# 05-AT86RF215IQ-FEM.net
KiCad netlist of a schematic drawn in Altium Designer
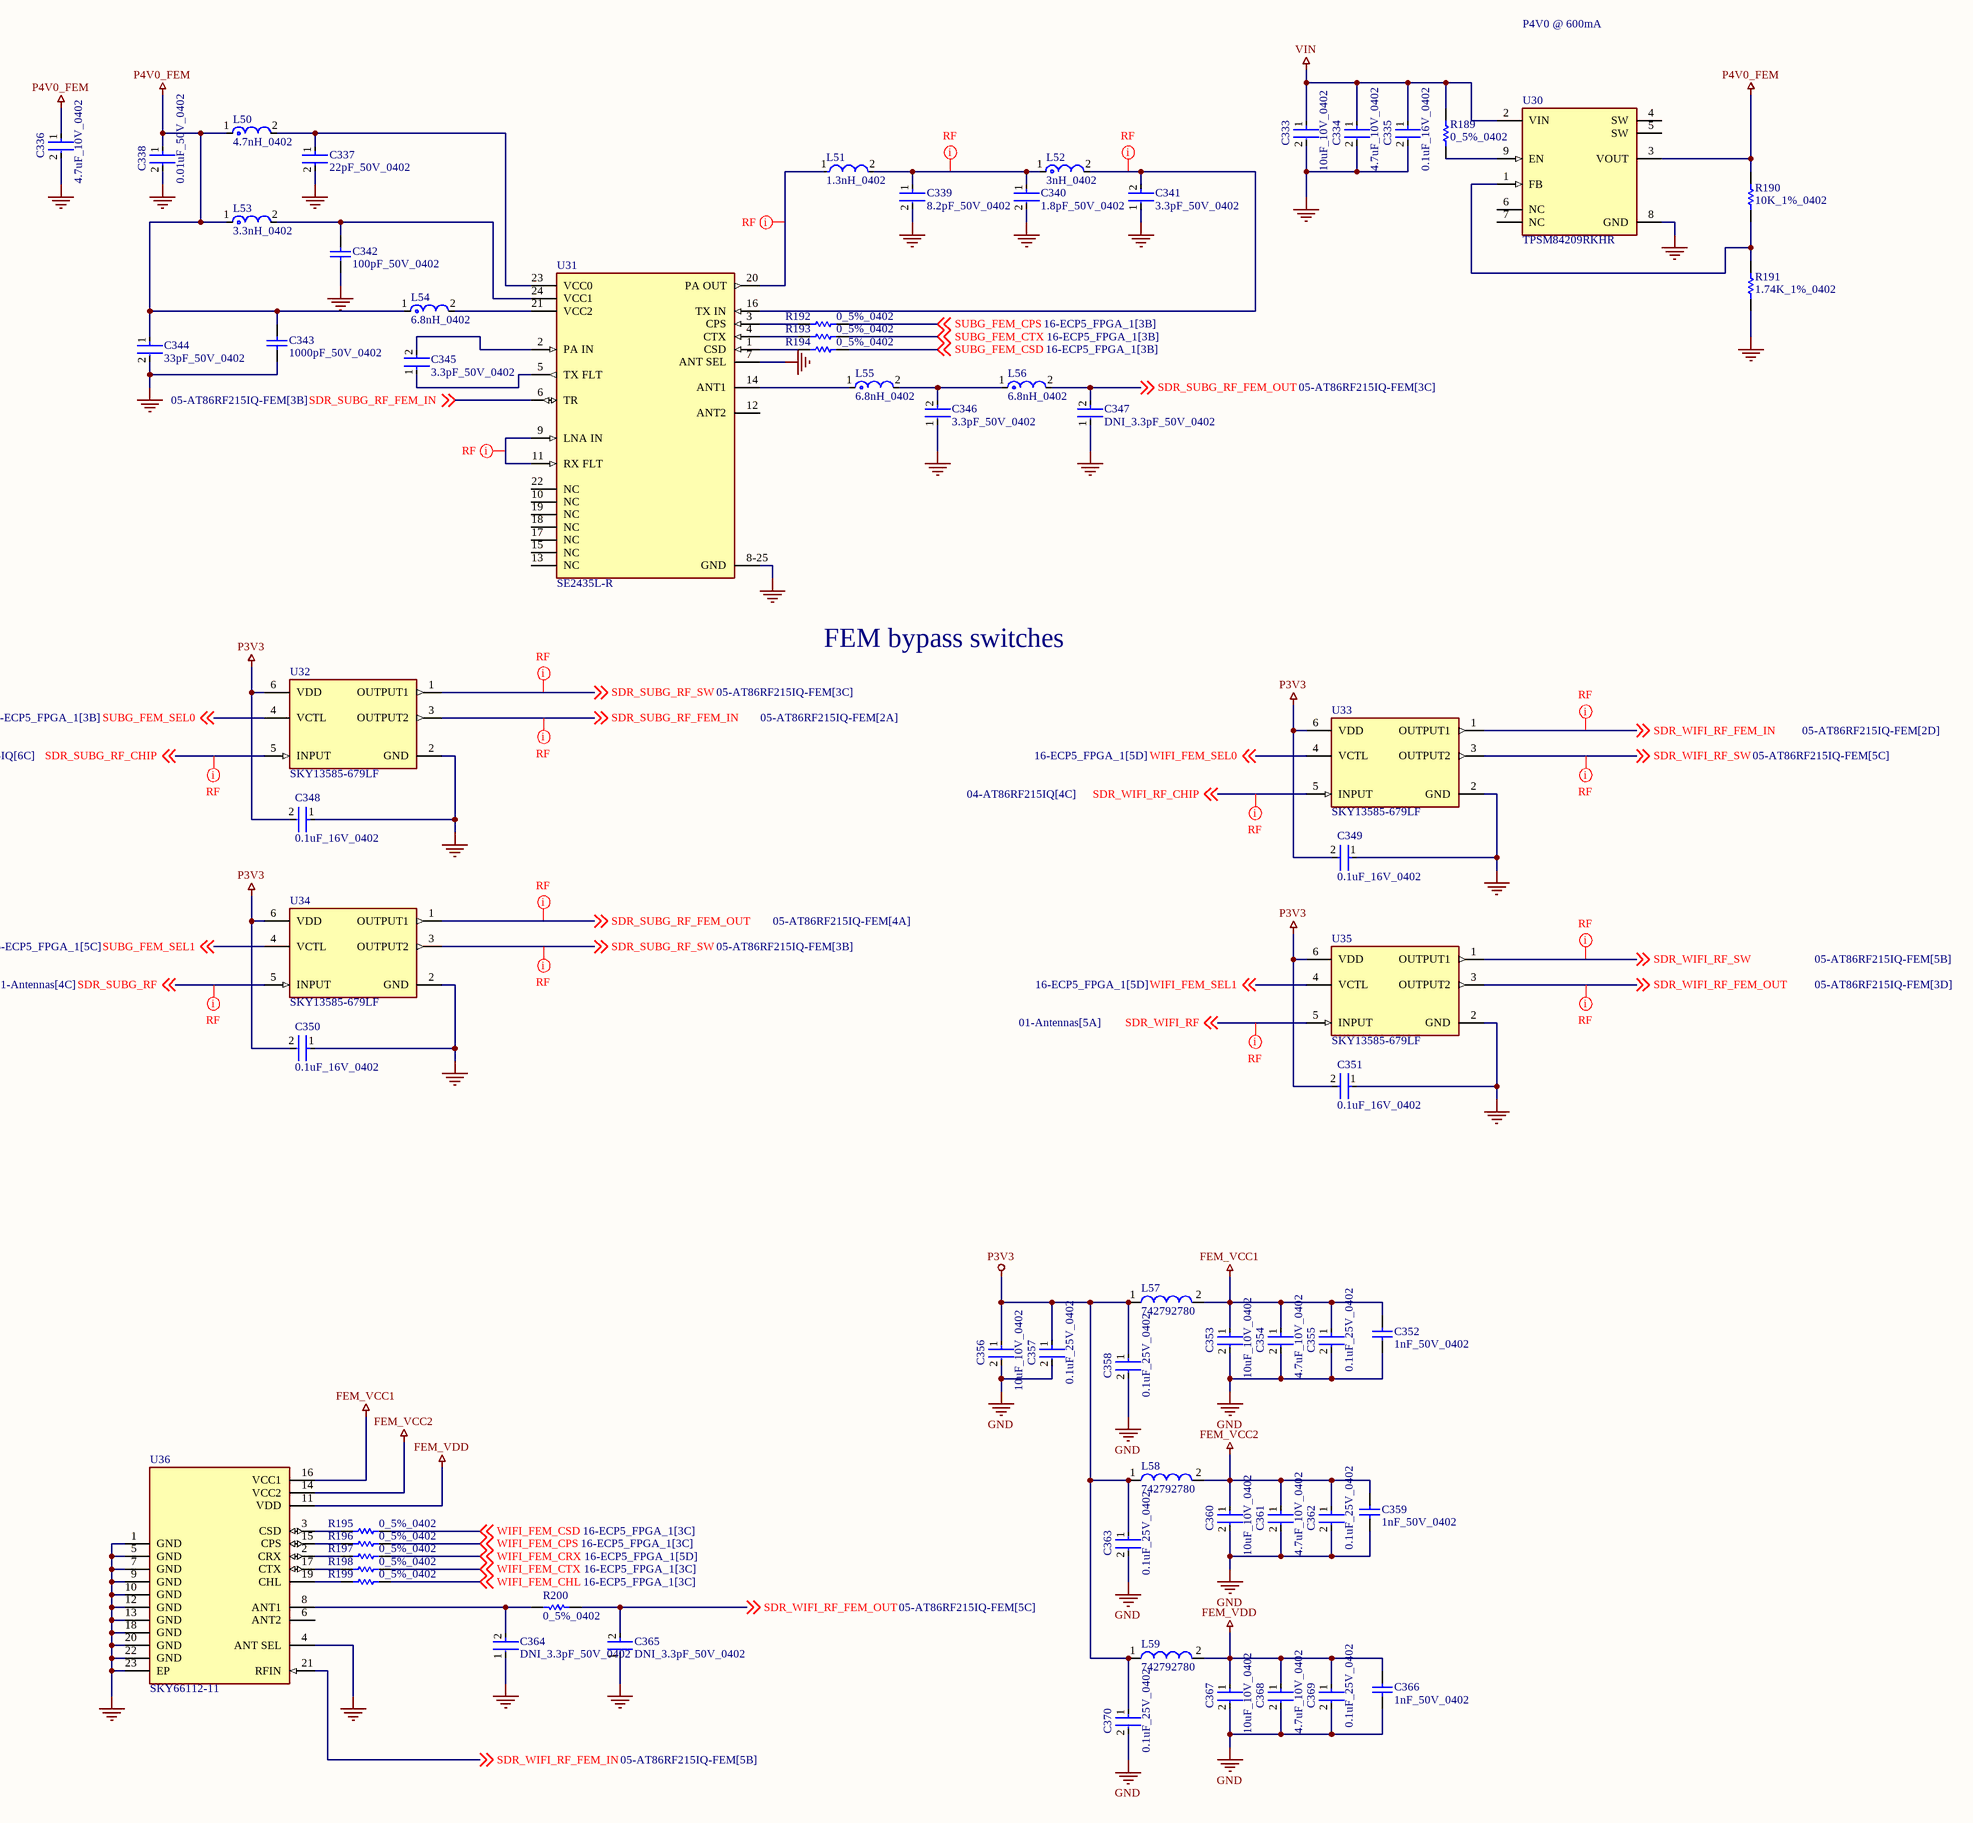
[diagram p0: 05-AT86RF215IQ-FEM.SchDoc]

(export (version "E")
  (design (tool "Eeschema 10.0.6"))
  (components
    (comp (ref "C333")
      (value "10uF_10V_0402")
      (footprint "FP-CL05A106MP5NUNC-MFG")
      (description "CAP CER 10UF 10V X5R 0402")
      (fields
        (field (name "OCTOPART") "https://octopart.com/cl05a106mp5nunc-samsung-22457395")
        (field (name "TOLERANCE") "20%")
      )
      (libsource (lib "Altium Content Vault") (part "b4654b650e69147ec39a6b967a45e02"))
    )
    (comp (ref "C334")
      (value "4.7uF_10V_0402")
      (footprint "FP-C1005-050-0_15-MFG")
      (description "CAP CER 4.7UF 10V X5R 0402")
      (fields (field (name "TOLERANCE") "10%"))
      (libsource (lib "Altium Content Vault") (part "b4654b650e69147ec39a6b967a45e02"))
    )
    (comp (ref "C335")
      (value "0.1uF_16V_0402")
      (footprint "FP-C0402-BB-MFG")
      (description "CAP CER 0.1UF 16V 5% X7R 0402")
      (fields
        (field (name "MANUFACTURER") "Kemet")
        (field (name "MANUFACTURER PART NUMBER") "C0402C104J4RACTU")
      )
      (libsource (lib "Altium Content Vault") (part "b4654b650e69147ec39a6b967a45e02"))
    )
    (comp (ref "C336")
      (value "4.7uF_10V_0402")
      (footprint "FP-C1005-050-0_15-MFG")
      (description "CAP CER 4.7UF 10V X5R 0402")
      (fields (field (name "TOLERANCE") "10%"))
      (libsource (lib "Altium Content Vault") (part "b4654b650e69147ec39a6b967a45e02"))
    )
    (comp (ref "C337")
      (value "22pF_50V_0402")
      (footprint "FP-0402-L_1_0_1-W_0_5_0_1-MFG")
      (description "General Purpose Ceramic Capacitor, 0402, 22pF, 5%, C0G, 30ppm/°C, 50V")
      (fields (field (name "VOLTAGE") "50V") (field (name "TOLERANCE") "5%"))
      (libsource (lib "Altium Content Vault") (part "b4654b650e69147ec39a6b967a45e02"))
    )
    (comp (ref "C338")
      (value "0.01uF_50V_0402")
      (footprint "FP-GCM155-0_05-IPC_C")
      (description "Ceramic Capacitor for Automotive 10nF ±10% 50VDC X7R 0402 Paper T/R")
      (fields (field (name "TOLERANCE") "10%") (field (name "VOLTAGE") "50V"))
      (libsource (lib "Altium Content Vault") (part "02cd4be3c70576c341d710602a673aa"))
    )
    (comp (ref "C339")
      (value "8.2pF_50V_0402")
      (footprint "FP-GJM155-0_05-IPC_C")
      (description "Multi-Layer Ceramic Capacitor 8.2pF C0G  ±0.25pF 0402 Paper T/R")
      (fields (field (name "VOLTAGE") "50V"))
      (libsource (lib "Altium Content Vault") (part "02cd4be3c70576c341d710602a673aa"))
    )
    (comp (ref "C340")
      (value "1.8pF_50V_0402")
      (footprint "FP-GJM155-0_05-IPC_B")
      (description "Multi-Layer Ceramic Capacitor 1.8pF C0G  ±0.1pF 0402 Paper T/R")
      (fields (field (name "VOLTAGE") "50V"))
      (libsource (lib "Altium Content Vault") (part "02cd4be3c70576c341d710602a673aa"))
    )
    (comp (ref "C341")
      (value "3.3pF_50V_0402")
      (footprint "FP-CBR04C-MFG")
      (description "CAP CER 3.3PF 50V C0G/NP0 0402")
      (fields (field (name "MANUFACTURER PART NUMBER") "CBR04C339C5GAC") (field (name "TOLERANCE") "0.25 pF"))
      (libsource (lib "Altium Content Vault") (part "236180d848d6139a670b325ea6854c9"))
    )
    (comp (ref "C342")
      (value "100pF_50V_0402")
      (footprint "CAPC1005X55X25ML05T10")
      (fields (field (name "MANUFACTURER") "Murata") (field (name "PART NUMBER") "GRM1555C1H101JA01D"))
      (libsource (lib "Altium Content Vault") (part "CAP"))
    )
    (comp (ref "C343")
      (value "1000pF_50V_0402")
      (footprint "CAPC1005X55X25ML5T10")
      (description "Chip Capacitor, 1 nF, +/- 10%, 50 V, -55 to 125 degC, 0402 (1005 Metric), RoHS, Tape and Reel")
      (fields (field (name "TOLERANCE") "10%"))
      (libsource (lib "Altium Content Vault") (part "CAP-NP-2"))
    )
    (comp (ref "C344")
      (value "33pF_50V_0402")
      (footprint "FP-0402-L_1_0_1-W_0_5_0_1-IPC_A")
      (description "General Purpose Ceramic Capacitor, 0402, 33pF, 5%, C0G, 30ppm/°C, 50V")
      (fields (field (name "TOLERANCE") "5%") (field (name "VOLTAGE") "50V"))
      (libsource (lib "Altium Content Vault") (part "b4654b650e69147ec39a6b967a45e02"))
    )
    (comp (ref "C345")
      (value "3.3pF_50V_0402")
      (footprint "FP-GCM155-0_05-IPC_B")
      (description "Ceramic Capacitor for Automotive 3.3pF ±0.25pF 50VDC C0G 0402 Paper T/R")
      (libsource (lib "Altium Content Vault") (part "02cd4be3c70576c341d710602a673aa"))
    )
    (comp (ref "C346")
      (value "3.3pF_50V_0402")
      (footprint "FP-CBR04C-MFG")
      (description "CAP CER 3.3PF 50V C0G/NP0 0402")
      (fields (field (name "MANUFACTURER PART NUMBER") "CBR04C339C5GAC") (field (name "TOLERANCE") "0.25 pF"))
      (libsource (lib "Altium Content Vault") (part "236180d848d6139a670b325ea6854c9"))
    )
    (comp (ref "C347")
      (value "DNI_3.3pF_50V_0402")
      (footprint "FP-CBR04C-MFG")
      (description "CAP CER 3.3PF 50V C0G/NP0 0402")
      (fields (field (name "MANUFACTURER PART NUMBER") "CBR04C339C5GAC") (field (name "TOLERANCE") "0.25 pF"))
      (libsource (lib "Altium Content Vault") (part "236180d848d6139a670b325ea6854c9"))
    )
    (comp (ref "C348")
      (value "0.1uF_16V_0402")
      (footprint "FP-C0402-BB-MFG")
      (description "CAP CER 0.1UF 16V 5% X7R 0402")
      (fields
        (field (name "MANUFACTURER") "Kemet")
        (field (name "MANUFACTURER PART NUMBER") "C0402C104J4RACTU")
      )
      (libsource (lib "Altium Content Vault") (part "b4654b650e69147ec39a6b967a45e02"))
    )
    (comp (ref "C349")
      (value "0.1uF_16V_0402")
      (footprint "FP-C0402-BB-MFG")
      (description "CAP CER 0.1UF 16V 5% X7R 0402")
      (fields
        (field (name "MANUFACTURER") "Kemet")
        (field (name "MANUFACTURER PART NUMBER") "C0402C104J4RACTU")
      )
      (libsource (lib "Altium Content Vault") (part "b4654b650e69147ec39a6b967a45e02"))
    )
    (comp (ref "C350")
      (value "0.1uF_16V_0402")
      (footprint "FP-C0402-BB-MFG")
      (description "CAP CER 0.1UF 16V 5% X7R 0402")
      (fields
        (field (name "MANUFACTURER") "Kemet")
        (field (name "MANUFACTURER PART NUMBER") "C0402C104J4RACTU")
      )
      (libsource (lib "Altium Content Vault") (part "b4654b650e69147ec39a6b967a45e02"))
    )
    (comp (ref "C351")
      (value "0.1uF_16V_0402")
      (footprint "FP-C0402-BB-MFG")
      (description "CAP CER 0.1UF 16V 5% X7R 0402")
      (fields
        (field (name "MANUFACTURER") "Kemet")
        (field (name "MANUFACTURER PART NUMBER") "C0402C104J4RACTU")
      )
      (libsource (lib "Altium Content Vault") (part "b4654b650e69147ec39a6b967a45e02"))
    )
    (comp (ref "C352")
      (value "1nF_50V_0402")
      (footprint "CAPC1005X55X25ML5T10")
      (description "Chip Capacitor, 1 nF, +/- 10%, 50 V, -55 to 125 degC, 0402 (1005 Metric), RoHS, Tape and Reel")
      (fields (field (name "TOLERANCE") "10%"))
      (libsource (lib "Altium Content Vault") (part "CAP-NP-2"))
    )
    (comp (ref "C353")
      (value "10uF_10V_0402")
      (footprint "FP-CL05A106MP5NUNC-MFG")
      (description "CAP CER 10UF 10V X5R 0402")
      (fields
        (field (name "OCTOPART") "https://octopart.com/cl05a106mp5nunc-samsung-22457395")
        (field (name "TOLERANCE") "20%")
      )
      (libsource (lib "Altium Content Vault") (part "b4654b650e69147ec39a6b967a45e02"))
    )
    (comp (ref "C354")
      (value "4.7uF_10V_0402")
      (footprint "FP-C1005-050-0_15-MFG")
      (description "CAP CER 4.7UF 10V X5R 0402")
      (fields (field (name "TOLERANCE") "10%"))
      (libsource (lib "Altium Content Vault") (part "b4654b650e69147ec39a6b967a45e02"))
    )
    (comp (ref "C355")
      (value "0.1uF_25V_0402")
      (footprint "FP-0402-L_1_0_1-W_0_5_0_1-IPC_C")
      (description "General Purpose Ceramic Capacitor, 0402, 100nF, 10%, X7R, 15%, 25V")
      (fields (field (name "VOLTAGE") "25V") (field (name "TOLERANCE") "10%"))
      (libsource (lib "Altium Content Vault") (part "b4654b650e69147ec39a6b967a45e02"))
    )
    (comp (ref "C356")
      (value "10uF_10V_0402")
      (footprint "FP-CL05A106MP5NUNC-MFG")
      (description "CAP CER 10UF 10V X5R 0402")
      (fields
        (field (name "OCTOPART") "https://octopart.com/cl05a106mp5nunc-samsung-22457395")
        (field (name "TOLERANCE") "20%")
      )
      (libsource (lib "Altium Content Vault") (part "b4654b650e69147ec39a6b967a45e02"))
    )
    (comp (ref "C357")
      (value "0.1uF_25V_0402")
      (footprint "FP-0402-L_1_0_1-W_0_5_0_1-IPC_C")
      (description "General Purpose Ceramic Capacitor, 0402, 100nF, 10%, X7R, 15%, 25V")
      (fields (field (name "VOLTAGE") "25V") (field (name "TOLERANCE") "10%"))
      (libsource (lib "Altium Content Vault") (part "b4654b650e69147ec39a6b967a45e02"))
    )
    (comp (ref "C358")
      (value "0.1uF_25V_0402")
      (footprint "FP-0402-L_1_0_1-W_0_5_0_1-IPC_C")
      (description "General Purpose Ceramic Capacitor, 0402, 100nF, 10%, X7R, 15%, 25V")
      (fields (field (name "VOLTAGE") "25V") (field (name "TOLERANCE") "10%"))
      (libsource (lib "Altium Content Vault") (part "b4654b650e69147ec39a6b967a45e02"))
    )
    (comp (ref "C359")
      (value "1nF_50V_0402")
      (footprint "CAPC1005X55X25ML5T10")
      (description "Chip Capacitor, 1 nF, +/- 10%, 50 V, -55 to 125 degC, 0402 (1005 Metric), RoHS, Tape and Reel")
      (fields (field (name "TOLERANCE") "10%"))
      (libsource (lib "Altium Content Vault") (part "CAP-NP-2"))
    )
    (comp (ref "C360")
      (value "10uF_10V_0402")
      (footprint "FP-CL05A106MP5NUNC-MFG")
      (description "CAP CER 10UF 10V X5R 0402")
      (fields
        (field (name "OCTOPART") "https://octopart.com/cl05a106mp5nunc-samsung-22457395")
        (field (name "TOLERANCE") "20%")
      )
      (libsource (lib "Altium Content Vault") (part "b4654b650e69147ec39a6b967a45e02"))
    )
    (comp (ref "C361")
      (value "4.7uF_10V_0402")
      (footprint "FP-C1005-050-0_15-MFG")
      (description "CAP CER 4.7UF 10V X5R 0402")
      (fields (field (name "TOLERANCE") "10%"))
      (libsource (lib "Altium Content Vault") (part "b4654b650e69147ec39a6b967a45e02"))
    )
    (comp (ref "C362")
      (value "0.1uF_25V_0402")
      (footprint "FP-0402-L_1_0_1-W_0_5_0_1-IPC_C")
      (description "General Purpose Ceramic Capacitor, 0402, 100nF, 10%, X7R, 15%, 25V")
      (fields (field (name "VOLTAGE") "25V") (field (name "TOLERANCE") "10%"))
      (libsource (lib "Altium Content Vault") (part "b4654b650e69147ec39a6b967a45e02"))
    )
    (comp (ref "C363")
      (value "0.1uF_25V_0402")
      (footprint "FP-0402-L_1_0_1-W_0_5_0_1-IPC_C")
      (description "General Purpose Ceramic Capacitor, 0402, 100nF, 10%, X7R, 15%, 25V")
      (fields (field (name "VOLTAGE") "25V") (field (name "TOLERANCE") "10%"))
      (libsource (lib "Altium Content Vault") (part "b4654b650e69147ec39a6b967a45e02"))
    )
    (comp (ref "C364")
      (value "DNI_3.3pF_50V_0402")
      (footprint "FP-CBR04C-MFG")
      (description "CAP CER 3.3PF 50V C0G/NP0 0402")
      (fields (field (name "MANUFACTURER PART NUMBER") "CBR04C339C5GAC") (field (name "TOLERANCE") "0.25 pF"))
      (libsource (lib "Altium Content Vault") (part "236180d848d6139a670b325ea6854c9"))
    )
    (comp (ref "C365")
      (value "DNI_3.3pF_50V_0402")
      (footprint "FP-CBR04C-MFG")
      (description "CAP CER 3.3PF 50V C0G/NP0 0402")
      (fields (field (name "MANUFACTURER PART NUMBER") "CBR04C339C5GAC") (field (name "TOLERANCE") "0.25 pF"))
      (libsource (lib "Altium Content Vault") (part "236180d848d6139a670b325ea6854c9"))
    )
    (comp (ref "C366")
      (value "1nF_50V_0402")
      (footprint "CAPC1005X55X25ML5T10")
      (description "Chip Capacitor, 1 nF, +/- 10%, 50 V, -55 to 125 degC, 0402 (1005 Metric), RoHS, Tape and Reel")
      (fields (field (name "TOLERANCE") "10%"))
      (libsource (lib "Altium Content Vault") (part "CAP-NP-2"))
    )
    (comp (ref "C367")
      (value "10uF_10V_0402")
      (footprint "FP-CL05A106MP5NUNC-MFG")
      (description "CAP CER 10UF 10V X5R 0402")
      (fields
        (field (name "OCTOPART") "https://octopart.com/cl05a106mp5nunc-samsung-22457395")
        (field (name "TOLERANCE") "20%")
      )
      (libsource (lib "Altium Content Vault") (part "b4654b650e69147ec39a6b967a45e02"))
    )
    (comp (ref "C368")
      (value "4.7uF_10V_0402")
      (footprint "FP-C1005-050-0_15-MFG")
      (description "CAP CER 4.7UF 10V X5R 0402")
      (fields (field (name "TOLERANCE") "10%"))
      (libsource (lib "Altium Content Vault") (part "b4654b650e69147ec39a6b967a45e02"))
    )
    (comp (ref "C369")
      (value "0.1uF_25V_0402")
      (footprint "FP-0402-L_1_0_1-W_0_5_0_1-IPC_C")
      (description "General Purpose Ceramic Capacitor, 0402, 100nF, 10%, X7R, 15%, 25V")
      (fields (field (name "VOLTAGE") "25V") (field (name "TOLERANCE") "10%"))
      (libsource (lib "Altium Content Vault") (part "b4654b650e69147ec39a6b967a45e02"))
    )
    (comp (ref "C370")
      (value "0.1uF_25V_0402")
      (footprint "FP-0402-L_1_0_1-W_0_5_0_1-IPC_C")
      (description "General Purpose Ceramic Capacitor, 0402, 100nF, 10%, X7R, 15%, 25V")
      (fields (field (name "VOLTAGE") "25V") (field (name "TOLERANCE") "10%"))
      (libsource (lib "Altium Content Vault") (part "b4654b650e69147ec39a6b967a45e02"))
    )
    (comp (ref "L50")
      (value "4.7nH_0402")
      (footprint "FP-LQG15HH_02-IPC_B")
      (description "Multilayer type RF Inductor 4.7nH ±0.2nH 0.16Ω 700mA 0402")
      (libsource (lib "Altium Content Vault") (part "4cc4b267dca4c8e51f7102f422741d8"))
    )
    (comp (ref "L51")
      (value "1.3nH_0402")
      (footprint "FP-LQW15AN_00-W0_6-0_1-MFG")
      (description "Wire Wound RF Inductor 1.3nH ±0.2nH 1200mA 0.017Ω 0402 (1005)")
      (libsource (lib "Altium Content Vault") (part "725321dda6339637d4d059423bc1c3c"))
    )
    (comp (ref "L52")
      (value "3nH_0402")
      (footprint "FP-LQG15HH_02-IPC_A")
      (description "Multilayer type RF Inductor 3nH ±0.3nH 0.125Ω 800mA 0402")
      (libsource (lib "Altium Content Vault") (part "4cc4b267dca4c8e51f7102f422741d8"))
    )
    (comp (ref "L53")
      (value "3.3nH_0402")
      (footprint "FP-LQG15HH_02-IPC_B")
      (description "Multilayer type RF Inductor 3.3nH ±0.3nH 0.125Ω 800mA 0402")
      (libsource (lib "Altium Content Vault") (part "4cc4b267dca4c8e51f7102f422741d8"))
    )
    (comp (ref "L54")
      (value "6.8nH_0402")
      (footprint "FP-LQG15HH_02-IPC_A")
      (description "Multilayer type RF Inductor 6.8nH ±5% 0.22Ω 600mA 0402")
      (fields (field (name "TOLERANCE") "5%"))
      (libsource (lib "Altium Content Vault") (part "4cc4b267dca4c8e51f7102f422741d8"))
    )
    (comp (ref "L55")
      (value "6.8nH_0402")
      (footprint "FP-LQG15HH_02-IPC_A")
      (description "Multilayer type RF Inductor 6.8nH ±5% 0.22Ω 600mA 0402")
      (fields (field (name "TOLERANCE") "5%"))
      (libsource (lib "Altium Content Vault") (part "4cc4b267dca4c8e51f7102f422741d8"))
    )
    (comp (ref "L56")
      (value "6.8nH_0402")
      (footprint "FP-LQG15HH_02-IPC_A")
      (description "Multilayer type RF Inductor 6.8nH ±5% 0.22Ω 600mA 0402")
      (fields (field (name "TOLERANCE") "5%"))
      (libsource (lib "Altium Content Vault") (part "4cc4b267dca4c8e51f7102f422741d8"))
    )
    (comp (ref "L57")
      (value "742792780")
      (footprint "SMD-0402")
      (description "SMD EMI Suppression Ferrite Bead WE-CBF, Z = 220 Ohm")
      (libsource (lib "Altium Content Vault") (part "PAS-IND-INDUCTOR-2"))
    )
    (comp (ref "L58")
      (value "742792780")
      (footprint "SMD-0402")
      (description "SMD EMI Suppression Ferrite Bead WE-CBF, Z = 220 Ohm")
      (libsource (lib "Altium Content Vault") (part "PAS-IND-INDUCTOR-2"))
    )
    (comp (ref "L59")
      (value "742792780")
      (footprint "SMD-0402")
      (description "SMD EMI Suppression Ferrite Bead WE-CBF, Z = 220 Ohm")
      (libsource (lib "Altium Content Vault") (part "PAS-IND-INDUCTOR-2"))
    )
    (comp (ref "R189")
      (value "0_5%_0402")
      (footprint "RESC1005X40X25NL05T10")
      (fields (field (name "MANUFACTURER") "Panasonic") (field (name "PART NUMBER") "ERJ-U020R00X"))
      (libsource (lib "Altium Content Vault") (part "RES"))
    )
    (comp (ref "R190")
      (value "10K_1%_0402")
      (footprint "RESC1005X40X25LL05T10")
      (fields (field (name "PART NUMBER") "RC0402FR-0710KL") (field (name "MANUFACTURER") "Yageo / Phycomp"))
      (libsource (lib "Altium Content Vault") (part "RES"))
    )
    (comp (ref "R191")
      (value "1.74K_1%_0402")
      (footprint "RESC1005X40X25NL05T05")
      (fields (field (name "MANUFACTURER") "Panasonic") (field (name "PART NUMBER") "ERJ-2RKF1741X"))
      (libsource (lib "Altium Content Vault") (part "RES"))
    )
    (comp (ref "R192")
      (value "0_5%_0402")
      (footprint "RESC1005X40X25NL05T10")
      (fields (field (name "MANUFACTURER") "Panasonic") (field (name "PART NUMBER") "ERJ-U020R00X"))
      (libsource (lib "Altium Content Vault") (part "RES"))
    )
    (comp (ref "R193")
      (value "0_5%_0402")
      (footprint "RESC1005X40X25NL05T10")
      (fields (field (name "MANUFACTURER") "Panasonic") (field (name "PART NUMBER") "ERJ-U020R00X"))
      (libsource (lib "Altium Content Vault") (part "RES"))
    )
    (comp (ref "R194")
      (value "0_5%_0402")
      (footprint "RESC1005X40X25NL05T10")
      (fields (field (name "MANUFACTURER") "Panasonic") (field (name "PART NUMBER") "ERJ-U020R00X"))
      (libsource (lib "Altium Content Vault") (part "RES"))
    )
    (comp (ref "R195")
      (value "0_5%_0402")
      (footprint "RESC1005X40X25NL05T10")
      (fields (field (name "MANUFACTURER") "Panasonic") (field (name "PART NUMBER") "ERJ-U020R00X"))
      (libsource (lib "Altium Content Vault") (part "RES"))
    )
    (comp (ref "R196")
      (value "0_5%_0402")
      (footprint "RESC1005X40X25NL05T10")
      (fields (field (name "MANUFACTURER") "Panasonic") (field (name "PART NUMBER") "ERJ-U020R00X"))
      (libsource (lib "Altium Content Vault") (part "RES"))
    )
    (comp (ref "R197")
      (value "0_5%_0402")
      (footprint "RESC1005X40X25NL05T10")
      (fields (field (name "MANUFACTURER") "Panasonic") (field (name "PART NUMBER") "ERJ-U020R00X"))
      (libsource (lib "Altium Content Vault") (part "RES"))
    )
    (comp (ref "R198")
      (value "0_5%_0402")
      (footprint "RESC1005X40X25NL05T10")
      (fields (field (name "MANUFACTURER") "Panasonic") (field (name "PART NUMBER") "ERJ-U020R00X"))
      (libsource (lib "Altium Content Vault") (part "RES"))
    )
    (comp (ref "R199")
      (value "0_5%_0402")
      (footprint "RESC1005X40X25NL05T10")
      (fields (field (name "MANUFACTURER") "Panasonic") (field (name "PART NUMBER") "ERJ-U020R00X"))
      (libsource (lib "Altium Content Vault") (part "RES"))
    )
    (comp (ref "R200")
      (value "0_5%_0402")
      (footprint "RESC1005X40X25NL05T10")
      (fields (field (name "MANUFACTURER") "Panasonic") (field (name "PART NUMBER") "ERJ-U020R00X"))
      (libsource (lib "Altium Content Vault") (part "RES"))
    )
    (comp (ref "U30")
      (value "TPSM84209RKHR")
      (footprint "FP-RKH0009A-MFG")
      (description "DC DC CONVERTER 1.2-6V")
      (libsource (lib "Altium Content Vault") (part "5195406eaf4ebe97fbc3c0702d316f5"))
    )
    (comp (ref "U31")
      (value "SE2435L-R")
      (footprint "FP-SE2435L-R-MFG")
      (description "IC FRONT END 930MHZ ISM 24QFN")
      (libsource (lib "Altium Content Vault") (part "3362008c0bbccc1bfff27db7c35ca37"))
    )
    (comp (ref "U32")
      (value "SKY13585-679LF")
      (footprint "FP-SKY13585-679LF-MFG")
      (description "IC RF SWITCH SPDT 6GHZ 6MLPD")
      (libsource (lib "Altium Content Vault") (part "e67e48af39ab44f3294fce00d3e4f12"))
    )
    (comp (ref "U33")
      (value "SKY13585-679LF")
      (footprint "FP-SKY13585-679LF-MFG")
      (description "IC RF SWITCH SPDT 6GHZ 6MLPD")
      (libsource (lib "Altium Content Vault") (part "e67e48af39ab44f3294fce00d3e4f12"))
    )
    (comp (ref "U34")
      (value "SKY13585-679LF")
      (footprint "FP-SKY13585-679LF-MFG")
      (description "IC RF SWITCH SPDT 6GHZ 6MLPD")
      (libsource (lib "Altium Content Vault") (part "e67e48af39ab44f3294fce00d3e4f12"))
    )
    (comp (ref "U35")
      (value "SKY13585-679LF")
      (footprint "FP-SKY13585-679LF-MFG")
      (description "IC RF SWITCH SPDT 6GHZ 6MLPD")
      (libsource (lib "Altium Content Vault") (part "e67e48af39ab44f3294fce00d3e4f12"))
    )
    (comp (ref "U36")
      (value "SKY66112-11")
      (footprint "FP-SKY66112-11-MFG")
      (description "CONNECTED HOME/WEARABLEBLE+ZIGBE")
      (libsource (lib "Altium Content Vault") (part "5720c400725e47a8c642696010eb527"))
    )
  )
  (nets
    (net (code "1") (name "FEM_VCC1") (class "Default")
      (node (ref "C352") (pin "2") (pinfunction "2_2") (pintype "passive"))
      (node (ref "C353") (pin "1") (pinfunction "1_1") (pintype "passive"))
      (node (ref "C354") (pin "1") (pinfunction "1_1") (pintype "passive"))
      (node (ref "C355") (pin "1") (pinfunction "1_1") (pintype "passive"))
      (node (ref "L57") (pin "2") (pinfunction "2_2") (pintype "passive"))
      (node (ref "U36") (pin "16") (pinfunction "VCC1_16") (pintype "power_in"))
    )
    (net (code "2") (name "FEM_VCC2") (class "Default")
      (node (ref "C359") (pin "2") (pinfunction "2_2") (pintype "passive"))
      (node (ref "C360") (pin "1") (pinfunction "1_1") (pintype "passive"))
      (node (ref "C361") (pin "1") (pinfunction "1_1") (pintype "passive"))
      (node (ref "C362") (pin "1") (pinfunction "1_1") (pintype "passive"))
      (node (ref "L58") (pin "2") (pinfunction "2_2") (pintype "passive"))
      (node (ref "U36") (pin "14") (pinfunction "VCC2_14") (pintype "power_in"))
    )
    (net (code "3") (name "FEM_VDD") (class "Default")
      (node (ref "C366") (pin "2") (pinfunction "2_2") (pintype "passive"))
      (node (ref "C367") (pin "1") (pinfunction "1_1") (pintype "passive"))
      (node (ref "C368") (pin "1") (pinfunction "1_1") (pintype "passive"))
      (node (ref "C369") (pin "1") (pinfunction "1_1") (pintype "passive"))
      (node (ref "L59") (pin "2") (pinfunction "2_2") (pintype "passive"))
      (node (ref "U36") (pin "11") (pinfunction "VDD_11") (pintype "power_in"))
    )
    (net (code "4") (name "GND") (class "Default")
      (node (ref "C333") (pin "2") (pinfunction "2_2") (pintype "passive"))
      (node (ref "C334") (pin "2") (pinfunction "2_2") (pintype "passive"))
      (node (ref "C335") (pin "2") (pinfunction "2_2") (pintype "passive"))
      (node (ref "C336") (pin "2") (pinfunction "2_2") (pintype "passive"))
      (node (ref "C337") (pin "2") (pinfunction "2_2") (pintype "passive"))
      (node (ref "C338") (pin "2") (pinfunction "2_2") (pintype "passive"))
      (node (ref "C339") (pin "2") (pinfunction "2_2") (pintype "passive"))
      (node (ref "C340") (pin "2") (pinfunction "2_2") (pintype "passive"))
      (node (ref "C341") (pin "1") (pinfunction "1_1") (pintype "passive"))
      (node (ref "C342") (pin "1") (pinfunction "1_1") (pintype "passive"))
      (node (ref "C343") (pin "1") (pinfunction "1_1") (pintype "passive"))
      (node (ref "C344") (pin "2") (pinfunction "2_2") (pintype "passive"))
      (node (ref "C346") (pin "1") (pinfunction "1_1") (pintype "passive"))
      (node (ref "C347") (pin "1") (pinfunction "1_1") (pintype "passive"))
      (node (ref "C348") (pin "1") (pinfunction "1_1") (pintype "passive"))
      (node (ref "C349") (pin "1") (pinfunction "1_1") (pintype "passive"))
      (node (ref "C350") (pin "1") (pinfunction "1_1") (pintype "passive"))
      (node (ref "C351") (pin "1") (pinfunction "1_1") (pintype "passive"))
      (node (ref "C352") (pin "1") (pinfunction "1_1") (pintype "passive"))
      (node (ref "C353") (pin "2") (pinfunction "2_2") (pintype "passive"))
      (node (ref "C354") (pin "2") (pinfunction "2_2") (pintype "passive"))
      (node (ref "C355") (pin "2") (pinfunction "2_2") (pintype "passive"))
      (node (ref "C356") (pin "2") (pinfunction "2_2") (pintype "passive"))
      (node (ref "C357") (pin "2") (pinfunction "2_2") (pintype "passive"))
      (node (ref "C358") (pin "2") (pinfunction "2_2") (pintype "passive"))
      (node (ref "C359") (pin "1") (pinfunction "1_1") (pintype "passive"))
      (node (ref "C360") (pin "2") (pinfunction "2_2") (pintype "passive"))
      (node (ref "C361") (pin "2") (pinfunction "2_2") (pintype "passive"))
      (node (ref "C362") (pin "2") (pinfunction "2_2") (pintype "passive"))
      (node (ref "C363") (pin "2") (pinfunction "2_2") (pintype "passive"))
      (node (ref "C364") (pin "1") (pinfunction "1_1") (pintype "passive"))
      (node (ref "C365") (pin "1") (pinfunction "1_1") (pintype "passive"))
      (node (ref "C366") (pin "1") (pinfunction "1_1") (pintype "passive"))
      (node (ref "C367") (pin "2") (pinfunction "2_2") (pintype "passive"))
      (node (ref "C368") (pin "2") (pinfunction "2_2") (pintype "passive"))
      (node (ref "C369") (pin "2") (pinfunction "2_2") (pintype "passive"))
      (node (ref "C370") (pin "2") (pinfunction "2_2") (pintype "passive"))
      (node (ref "R191") (pin "1") (pinfunction "1_1") (pintype "passive"))
      (node (ref "U30") (pin "8") (pinfunction "GND_8") (pintype "power_in"))
      (node (ref "U31") (pin "7") (pinfunction "ANT_SEL_7") (pintype "passive"))
      (node (ref "U31") (pin "8-25") (pinfunction "GND_8-25") (pintype "power_in"))
      (node (ref "U32") (pin "2") (pinfunction "GND_2") (pintype "power_in"))
      (node (ref "U33") (pin "2") (pinfunction "GND_2") (pintype "power_in"))
      (node (ref "U34") (pin "2") (pinfunction "GND_2") (pintype "power_in"))
      (node (ref "U35") (pin "2") (pinfunction "GND_2") (pintype "power_in"))
      (node (ref "U36") (pin "1") (pinfunction "GND_1") (pintype "power_in"))
      (node (ref "U36") (pin "10") (pinfunction "GND_10") (pintype "power_in"))
      (node (ref "U36") (pin "12") (pinfunction "GND_12") (pintype "power_in"))
      (node (ref "U36") (pin "13") (pinfunction "GND_13") (pintype "power_in"))
      (node (ref "U36") (pin "18") (pinfunction "GND_18") (pintype "power_in"))
      (node (ref "U36") (pin "20") (pinfunction "GND_20") (pintype "power_in"))
      (node (ref "U36") (pin "22") (pinfunction "GND_22") (pintype "power_in"))
      (node (ref "U36") (pin "23") (pinfunction "EP_23") (pintype "passive"))
      (node (ref "U36") (pin "4") (pinfunction "ANT_SEL_4") (pintype "passive"))
      (node (ref "U36") (pin "5") (pinfunction "GND_5") (pintype "power_in"))
      (node (ref "U36") (pin "7") (pinfunction "GND_7") (pintype "power_in"))
      (node (ref "U36") (pin "9") (pinfunction "GND_9") (pintype "power_in"))
    )
    (net (code "5") (name "Net-(C339-Pad1)") (class "Default")
      (node (ref "C339") (pin "1") (pinfunction "1_1") (pintype "passive"))
      (node (ref "C340") (pin "1") (pinfunction "1_1") (pintype "passive"))
      (node (ref "L51") (pin "2") (pinfunction "2_2") (pintype "passive"))
      (node (ref "L52") (pin "1") (pinfunction "1_1") (pintype "passive"))
    )
    (net (code "6") (name "Net-(C346-Pad2)") (class "Default")
      (node (ref "C346") (pin "2") (pinfunction "2_2") (pintype "passive"))
      (node (ref "L55") (pin "2") (pinfunction "2_2") (pintype "passive"))
      (node (ref "L56") (pin "1") (pinfunction "1_1") (pintype "passive"))
    )
    (net (code "7") (name "Net-(U30-EN)") (class "Default")
      (node (ref "R189") (pin "1") (pinfunction "1_1") (pintype "passive"))
      (node (ref "U30") (pin "9") (pinfunction "EN_9") (pintype "input"))
    )
    (net (code "8") (name "Net-(U30-FB)") (class "Default")
      (node (ref "R190") (pin "1") (pinfunction "1_1") (pintype "passive"))
      (node (ref "R191") (pin "2") (pinfunction "2_2") (pintype "passive"))
      (node (ref "U30") (pin "1") (pinfunction "FB_1") (pintype "input"))
    )
    (net (code "9") (name "Net-(U31-ANT1)") (class "Default")
      (node (ref "L55") (pin "1") (pinfunction "1_1") (pintype "passive"))
      (node (ref "U31") (pin "14") (pinfunction "ANT1_14") (pintype "passive"))
    )
    (net (code "10") (name "Net-(U31-CPS)") (class "Default")
      (node (ref "R192") (pin "1") (pinfunction "1_1") (pintype "passive"))
      (node (ref "U31") (pin "3") (pinfunction "CPS_3") (pintype "input"))
    )
    (net (code "11") (name "Net-(U31-CSD)") (class "Default")
      (node (ref "R194") (pin "1") (pinfunction "1_1") (pintype "passive"))
      (node (ref "U31") (pin "1") (pinfunction "CSD_1") (pintype "input"))
    )
    (net (code "12") (name "Net-(U31-CTX)") (class "Default")
      (node (ref "R193") (pin "1") (pinfunction "1_1") (pintype "passive"))
      (node (ref "U31") (pin "4") (pinfunction "CTX_4") (pintype "input"))
    )
    (net (code "13") (name "Net-(U31-LNA_IN)") (class "Default")
      (node (ref "U31") (pin "11") (pinfunction "RX_FLT_11") (pintype "input"))
      (node (ref "U31") (pin "9") (pinfunction "LNA_IN_9") (pintype "input"))
    )
    (net (code "14") (name "Net-(U31-PA_IN)") (class "Default")
      (node (ref "C345") (pin "2") (pinfunction "2_2") (pintype "passive"))
      (node (ref "U31") (pin "2") (pinfunction "PA_IN_2") (pintype "input"))
    )
    (net (code "15") (name "Net-(U31-PA_OUT)") (class "Default")
      (node (ref "L51") (pin "1") (pinfunction "1_1") (pintype "passive"))
      (node (ref "U31") (pin "20") (pinfunction "PA_OUT_20") (pintype "output"))
    )
    (net (code "16") (name "Net-(U31-TX_FLT)") (class "Default")
      (node (ref "C345") (pin "1") (pinfunction "1_1") (pintype "passive"))
      (node (ref "U31") (pin "5") (pinfunction "TX_FLT_5") (pintype "output"))
    )
    (net (code "17") (name "Net-(U31-TX_IN)") (class "Default")
      (node (ref "C341") (pin "2") (pinfunction "2_2") (pintype "passive"))
      (node (ref "L52") (pin "2") (pinfunction "2_2") (pintype "passive"))
      (node (ref "U31") (pin "16") (pinfunction "TX_IN_16") (pintype "input"))
    )
    (net (code "18") (name "Net-(U31-VCC0)") (class "Default")
      (node (ref "C337") (pin "1") (pinfunction "1_1") (pintype "passive"))
      (node (ref "L50") (pin "2") (pinfunction "2_2") (pintype "passive"))
      (node (ref "U31") (pin "23") (pinfunction "VCC0_23") (pintype "power_in"))
    )
    (net (code "19") (name "Net-(U31-VCC1)") (class "Default")
      (node (ref "C342") (pin "2") (pinfunction "2_2") (pintype "passive"))
      (node (ref "L53") (pin "2") (pinfunction "2_2") (pintype "passive"))
      (node (ref "U31") (pin "24") (pinfunction "VCC1_24") (pintype "power_in"))
    )
    (net (code "20") (name "Net-(U31-VCC2)") (class "Default")
      (node (ref "L54") (pin "2") (pinfunction "2_2") (pintype "passive"))
      (node (ref "U31") (pin "21") (pinfunction "VCC2_21") (pintype "power_in"))
    )
    (net (code "21") (name "Net-(U36-ANT1)") (class "Default")
      (node (ref "C364") (pin "2") (pinfunction "2_2") (pintype "passive"))
      (node (ref "R200") (pin "2") (pinfunction "2_2") (pintype "passive"))
      (node (ref "U36") (pin "8") (pinfunction "ANT1_8") (pintype "passive"))
    )
    (net (code "22") (name "Net-(U36-CHL)") (class "Default")
      (node (ref "R199") (pin "1") (pinfunction "1_1") (pintype "passive"))
      (node (ref "U36") (pin "19") (pinfunction "CHL_19") (pintype "passive"))
    )
    (net (code "23") (name "Net-(U36-CPS)") (class "Default")
      (node (ref "R196") (pin "1") (pinfunction "1_1") (pintype "passive"))
      (node (ref "U36") (pin "15") (pinfunction "CPS_15") (pintype "bidirectional"))
    )
    (net (code "24") (name "Net-(U36-CRX)") (class "Default")
      (node (ref "R197") (pin "1") (pinfunction "1_1") (pintype "passive"))
      (node (ref "U36") (pin "2") (pinfunction "CRX_2") (pintype "bidirectional"))
    )
    (net (code "25") (name "Net-(U36-CSD)") (class "Default")
      (node (ref "R195") (pin "1") (pinfunction "1_1") (pintype "passive"))
      (node (ref "U36") (pin "3") (pinfunction "CSD_3") (pintype "bidirectional"))
    )
    (net (code "26") (name "Net-(U36-CTX)") (class "Default")
      (node (ref "R198") (pin "1") (pinfunction "1_1") (pintype "passive"))
      (node (ref "U36") (pin "17") (pinfunction "CTX_17") (pintype "bidirectional"))
    )
    (net (code "27") (name "P3V3") (class "Default")
      (node (ref "C348") (pin "2") (pinfunction "2_2") (pintype "passive"))
      (node (ref "C349") (pin "2") (pinfunction "2_2") (pintype "passive"))
      (node (ref "C350") (pin "2") (pinfunction "2_2") (pintype "passive"))
      (node (ref "C351") (pin "2") (pinfunction "2_2") (pintype "passive"))
      (node (ref "C356") (pin "1") (pinfunction "1_1") (pintype "passive"))
      (node (ref "C357") (pin "1") (pinfunction "1_1") (pintype "passive"))
      (node (ref "C358") (pin "1") (pinfunction "1_1") (pintype "passive"))
      (node (ref "C363") (pin "1") (pinfunction "1_1") (pintype "passive"))
      (node (ref "C370") (pin "1") (pinfunction "1_1") (pintype "passive"))
      (node (ref "L57") (pin "1") (pinfunction "1_1") (pintype "passive"))
      (node (ref "L58") (pin "1") (pinfunction "1_1") (pintype "passive"))
      (node (ref "L59") (pin "1") (pinfunction "1_1") (pintype "passive"))
      (node (ref "U32") (pin "6") (pinfunction "VDD_6") (pintype "power_in"))
      (node (ref "U33") (pin "6") (pinfunction "VDD_6") (pintype "power_in"))
      (node (ref "U34") (pin "6") (pinfunction "VDD_6") (pintype "power_in"))
      (node (ref "U35") (pin "6") (pinfunction "VDD_6") (pintype "power_in"))
    )
    (net (code "28") (name "P4V0_FEM") (class "Default")
      (node (ref "C336") (pin "1") (pinfunction "1_1") (pintype "passive"))
      (node (ref "C338") (pin "1") (pinfunction "1_1") (pintype "passive"))
      (node (ref "C343") (pin "2") (pinfunction "2_2") (pintype "passive"))
      (node (ref "C344") (pin "1") (pinfunction "1_1") (pintype "passive"))
      (node (ref "L50") (pin "1") (pinfunction "1_1") (pintype "passive"))
      (node (ref "L53") (pin "1") (pinfunction "1_1") (pintype "passive"))
      (node (ref "L54") (pin "1") (pinfunction "1_1") (pintype "passive"))
      (node (ref "R190") (pin "2") (pinfunction "2_2") (pintype "passive"))
      (node (ref "U30") (pin "3") (pinfunction "VOUT_3") (pintype "passive"))
    )
    (net (code "29") (name "SDR_SUBG_RF") (class "Default")
      (node (ref "U34") (pin "5") (pinfunction "INPUT_5") (pintype "input"))
    )
    (net (code "30") (name "SDR_SUBG_RF_CHIP") (class "Default")
      (node (ref "U32") (pin "5") (pinfunction "INPUT_5") (pintype "input"))
    )
    (net (code "31") (name "SDR_SUBG_RF_FEM_IN") (class "Default")
      (node (ref "U31") (pin "6") (pinfunction "TR_6") (pintype "bidirectional"))
      (node (ref "U32") (pin "3") (pinfunction "OUTPUT2_3") (pintype "output"))
    )
    (net (code "32") (name "SDR_SUBG_RF_FEM_OUT") (class "Default")
      (node (ref "C347") (pin "2") (pinfunction "2_2") (pintype "passive"))
      (node (ref "L56") (pin "2") (pinfunction "2_2") (pintype "passive"))
      (node (ref "U34") (pin "1") (pinfunction "OUTPUT1_1") (pintype "output"))
    )
    (net (code "33") (name "SDR_SUBG_RF_SW") (class "Default")
      (node (ref "U32") (pin "1") (pinfunction "OUTPUT1_1") (pintype "output"))
      (node (ref "U34") (pin "3") (pinfunction "OUTPUT2_3") (pintype "output"))
    )
    (net (code "34") (name "SDR_WIFI_RF") (class "Default")
      (node (ref "U35") (pin "5") (pinfunction "INPUT_5") (pintype "input"))
    )
    (net (code "35") (name "SDR_WIFI_RF_CHIP") (class "Default")
      (node (ref "U33") (pin "5") (pinfunction "INPUT_5") (pintype "input"))
    )
    (net (code "36") (name "SDR_WIFI_RF_FEM_IN") (class "Default")
      (node (ref "U33") (pin "1") (pinfunction "OUTPUT1_1") (pintype "output"))
      (node (ref "U36") (pin "21") (pinfunction "RFIN_21") (pintype "input"))
    )
    (net (code "37") (name "SDR_WIFI_RF_FEM_OUT") (class "Default")
      (node (ref "C365") (pin "2") (pinfunction "2_2") (pintype "passive"))
      (node (ref "R200") (pin "1") (pinfunction "1_1") (pintype "passive"))
      (node (ref "U35") (pin "3") (pinfunction "OUTPUT2_3") (pintype "output"))
    )
    (net (code "38") (name "SDR_WIFI_RF_SW") (class "Default")
      (node (ref "U33") (pin "3") (pinfunction "OUTPUT2_3") (pintype "output"))
      (node (ref "U35") (pin "1") (pinfunction "OUTPUT1_1") (pintype "output"))
    )
    (net (code "39") (name "SUBG_FEM_CPS") (class "Default")
      (node (ref "R192") (pin "2") (pinfunction "2_2") (pintype "passive"))
    )
    (net (code "40") (name "SUBG_FEM_CSD") (class "Default")
      (node (ref "R194") (pin "2") (pinfunction "2_2") (pintype "passive"))
    )
    (net (code "41") (name "SUBG_FEM_CTX") (class "Default")
      (node (ref "R193") (pin "2") (pinfunction "2_2") (pintype "passive"))
    )
    (net (code "42") (name "SUBG_FEM_SEL0") (class "Default")
      (node (ref "U32") (pin "4") (pinfunction "VCTL_4") (pintype "power_in"))
    )
    (net (code "43") (name "SUBG_FEM_SEL1") (class "Default")
      (node (ref "U34") (pin "4") (pinfunction "VCTL_4") (pintype "power_in"))
    )
    (net (code "44") (name "VIN") (class "Default")
      (node (ref "C333") (pin "1") (pinfunction "1_1") (pintype "passive"))
      (node (ref "C334") (pin "1") (pinfunction "1_1") (pintype "passive"))
      (node (ref "C335") (pin "1") (pinfunction "1_1") (pintype "passive"))
      (node (ref "R189") (pin "2") (pinfunction "2_2") (pintype "passive"))
      (node (ref "U30") (pin "2") (pinfunction "VIN_2") (pintype "power_in"))
    )
    (net (code "45") (name "WIFI_FEM_CHL") (class "Default")
      (node (ref "R199") (pin "2") (pinfunction "2_2") (pintype "passive"))
    )
    (net (code "46") (name "WIFI_FEM_CPS") (class "Default")
      (node (ref "R196") (pin "2") (pinfunction "2_2") (pintype "passive"))
    )
    (net (code "47") (name "WIFI_FEM_CRX") (class "Default")
      (node (ref "R197") (pin "2") (pinfunction "2_2") (pintype "passive"))
    )
    (net (code "48") (name "WIFI_FEM_CSD") (class "Default")
      (node (ref "R195") (pin "2") (pinfunction "2_2") (pintype "passive"))
    )
    (net (code "49") (name "WIFI_FEM_CTX") (class "Default")
      (node (ref "R198") (pin "2") (pinfunction "2_2") (pintype "passive"))
    )
    (net (code "50") (name "WIFI_FEM_SEL0") (class "Default")
      (node (ref "U33") (pin "4") (pinfunction "VCTL_4") (pintype "power_in"))
    )
    (net (code "51") (name "WIFI_FEM_SEL1") (class "Default")
      (node (ref "U35") (pin "4") (pinfunction "VCTL_4") (pintype "power_in"))
    )
    (net (code "52") (name "unconnected-(U30-NC-Pad6)") (class "Default")
      (node (ref "U30") (pin "6") (pinfunction "NC_6") (pintype "passive"))
    )
    (net (code "53") (name "unconnected-(U30-NC-Pad7)") (class "Default")
      (node (ref "U30") (pin "7") (pinfunction "NC_7") (pintype "passive"))
    )
    (net (code "54") (name "unconnected-(U30-SW-Pad4)") (class "Default")
      (node (ref "U30") (pin "4") (pinfunction "SW_4") (pintype "power_in"))
    )
    (net (code "55") (name "unconnected-(U30-SW-Pad5)") (class "Default")
      (node (ref "U30") (pin "5") (pinfunction "SW_5") (pintype "power_in"))
    )
    (net (code "56") (name "unconnected-(U31-ANT2-Pad12)") (class "Default")
      (node (ref "U31") (pin "12") (pinfunction "ANT2_12") (pintype "passive"))
    )
    (net (code "57") (name "unconnected-(U31-NC-Pad10)") (class "Default")
      (node (ref "U31") (pin "10") (pinfunction "NC_10") (pintype "passive"))
    )
    (net (code "58") (name "unconnected-(U31-NC-Pad13)") (class "Default")
      (node (ref "U31") (pin "13") (pinfunction "NC_13") (pintype "passive"))
    )
    (net (code "59") (name "unconnected-(U31-NC-Pad15)") (class "Default")
      (node (ref "U31") (pin "15") (pinfunction "NC_15") (pintype "passive"))
    )
    (net (code "60") (name "unconnected-(U31-NC-Pad17)") (class "Default")
      (node (ref "U31") (pin "17") (pinfunction "NC_17") (pintype "passive"))
    )
    (net (code "61") (name "unconnected-(U31-NC-Pad18)") (class "Default")
      (node (ref "U31") (pin "18") (pinfunction "NC_18") (pintype "passive"))
    )
    (net (code "62") (name "unconnected-(U31-NC-Pad19)") (class "Default")
      (node (ref "U31") (pin "19") (pinfunction "NC_19") (pintype "passive"))
    )
    (net (code "63") (name "unconnected-(U31-NC-Pad22)") (class "Default")
      (node (ref "U31") (pin "22") (pinfunction "NC_22") (pintype "passive"))
    )
    (net (code "64") (name "unconnected-(U36-ANT2-Pad6)") (class "Default")
      (node (ref "U36") (pin "6") (pinfunction "ANT2_6") (pintype "passive"))
    )
  )
)
